# 8266_DIYIOT_Board_B_DS_V_G.net
KiCad netlist of a schematic drawn in EAGLE
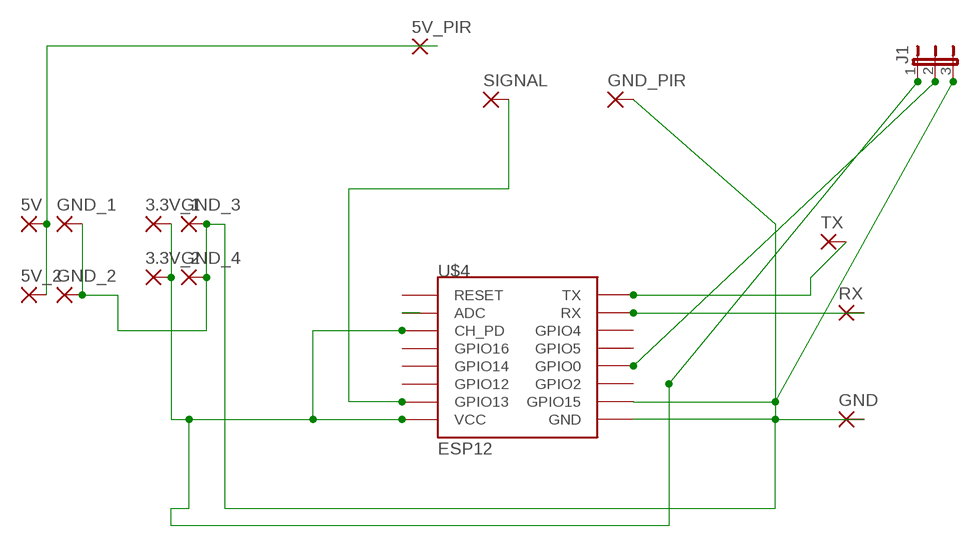
[diagram p0: schematic, sheet 1]

(export (version "E")
  (design (tool "Eeschema 10.0.6"))
  (components
    (comp (ref "3.3V_1")
      (value "2,15/1,0")
      (footprint "eagle-import:2,15_1,0")
      (libsource (lib "eagle-import") (part "2,15/1,0"))
    )
    (comp (ref "3.3V_2")
      (value "2,15/1,0")
      (footprint "eagle-import:2,15_1,0")
      (libsource (lib "eagle-import") (part "2,15/1,0"))
    )
    (comp (ref "5V")
      (value "2,15/1,0")
      (footprint "eagle-import:2,15_1,0")
      (libsource (lib "eagle-import") (part "2,15/1,0"))
    )
    (comp (ref "5V_2")
      (value "2,15/1,0")
      (footprint "eagle-import:2,15_1,0")
      (libsource (lib "eagle-import") (part "2,15/1,0"))
    )
    (comp (ref "5V_PIR")
      (value "2,15/1,0")
      (footprint "eagle-import:2,15_1,0")
      (libsource (lib "eagle-import") (part "2,15/1,0"))
    )
    (comp (ref "GND")
      (value "2,15/1,0")
      (footprint "eagle-import:2,15_1,0")
      (libsource (lib "eagle-import") (part "2,15/1,0"))
    )
    (comp (ref "GND_1")
      (value "2,15/1,0")
      (footprint "eagle-import:2,15_1,0")
      (libsource (lib "eagle-import") (part "2,15/1,0"))
    )
    (comp (ref "GND_2")
      (value "2,15/1,0")
      (footprint "eagle-import:2,15_1,0")
      (libsource (lib "eagle-import") (part "2,15/1,0"))
    )
    (comp (ref "GND_3")
      (value "2,15/1,0")
      (footprint "eagle-import:2,15_1,0")
      (libsource (lib "eagle-import") (part "2,15/1,0"))
    )
    (comp (ref "GND_4")
      (value "2,15/1,0")
      (footprint "eagle-import:2,15_1,0")
      (libsource (lib "eagle-import") (part "2,15/1,0"))
    )
    (comp (ref "GND_PIR")
      (value "2,15/1,0")
      (footprint "eagle-import:2,15_1,0")
      (libsource (lib "eagle-import") (part "2,15/1,0"))
    )
    (comp (ref "J1")
      (value "JP2E")
      (footprint "eagle-import:JP2")
      (libsource (lib "eagle-import") (part "JP2E"))
    )
    (comp (ref "RX")
      (value "2,15/1,0")
      (footprint "eagle-import:2,15_1,0")
      (libsource (lib "eagle-import") (part "2,15/1,0"))
    )
    (comp (ref "SIGNAL")
      (value "2,15/1,0")
      (footprint "eagle-import:2,15_1,0")
      (libsource (lib "eagle-import") (part "2,15/1,0"))
    )
    (comp (ref "TX")
      (value "2,15/1,0")
      (footprint "eagle-import:2,15_1,0")
      (libsource (lib "eagle-import") (part "2,15/1,0"))
    )
    (comp (ref "U$4")
      (value "ESP12")
      (footprint "eagle-import:ESP12")
      (libsource (lib "eagle-import") (part "ESP12"))
    )
  )
  (nets
    (net (code "1") (name "/5V") (class "Default")
      (node (ref "5V") (pin "1") (pinfunction "P_1") (pintype "passive"))
      (node (ref "5V_2") (pin "1") (pinfunction "P_1") (pintype "passive"))
      (node (ref "5V_PIR") (pin "1") (pinfunction "P_1") (pintype "passive"))
      (node (ref "GND") (pin "1") (pinfunction "P_1") (pintype "passive"))
      (node (ref "GND_1") (pin "1") (pinfunction "P_1") (pintype "passive"))
      (node (ref "GND_2") (pin "1") (pinfunction "P_1") (pintype "passive"))
      (node (ref "GND_3") (pin "1") (pinfunction "P_1") (pintype "passive"))
      (node (ref "GND_4") (pin "1") (pinfunction "P_1") (pintype "passive"))
      (node (ref "GND_PIR") (pin "1") (pinfunction "P_1") (pintype "passive"))
      (node (ref "J1") (pin "3") (pinfunction "3_3") (pintype "passive"))
      (node (ref "U$4") (pin "GND") (pinfunction "GND_GND") (pintype "bidirectional"))
      (node (ref "U$4") (pin "GPIO15") (pinfunction "GPIO15_GPIO15") (pintype "bidirectional"))
    )
    (net (code "2") (name "Net-(3.3V_1-P)") (class "Default")
      (node (ref "3.3V_1") (pin "1") (pinfunction "P_1") (pintype "passive"))
      (node (ref "3.3V_2") (pin "1") (pinfunction "P_1") (pintype "passive"))
      (node (ref "J1") (pin "1") (pinfunction "1_1") (pintype "passive"))
      (node (ref "U$4") (pin "CH_PD") (pinfunction "CH_PD_CH_PD") (pintype "bidirectional"))
      (node (ref "U$4") (pin "VCC") (pinfunction "VCC_VCC") (pintype "bidirectional"))
    )
    (net (code "3") (name "Net-(J1-Pad2)") (class "Default")
      (node (ref "J1") (pin "2") (pinfunction "2_2") (pintype "passive"))
      (node (ref "U$4") (pin "GPIO0") (pinfunction "GPIO0_GPIO0") (pintype "bidirectional"))
    )
    (net (code "4") (name "Net-(RX-P)") (class "Default")
      (node (ref "RX") (pin "1") (pinfunction "P_1") (pintype "passive"))
      (node (ref "U$4") (pin "RX") (pinfunction "RX_RX") (pintype "bidirectional"))
    )
    (net (code "5") (name "Net-(SIGNAL-P)") (class "Default")
      (node (ref "SIGNAL") (pin "1") (pinfunction "P_1") (pintype "passive"))
      (node (ref "U$4") (pin "GPIO13") (pinfunction "GPIO13_GPIO13") (pintype "bidirectional"))
    )
    (net (code "6") (name "Net-(TX-P)") (class "Default")
      (node (ref "TX") (pin "1") (pinfunction "P_1") (pintype "passive"))
      (node (ref "U$4") (pin "TX") (pinfunction "TX_TX") (pintype "bidirectional"))
    )
    (net (code "7") (name "unconnected-(U$4-PadADC)") (class "Default")
      (node (ref "U$4") (pin "ADC") (pinfunction "ADC_ADC") (pintype "bidirectional"))
    )
    (net (code "8") (name "unconnected-(U$4-PadGPIO2)") (class "Default")
      (node (ref "U$4") (pin "GPIO2") (pinfunction "GPIO2_GPIO2") (pintype "bidirectional"))
    )
    (net (code "9") (name "unconnected-(U$4-PadGPIO4)") (class "Default")
      (node (ref "U$4") (pin "GPIO4") (pinfunction "GPIO4_GPIO4") (pintype "bidirectional"))
    )
    (net (code "10") (name "unconnected-(U$4-PadGPIO5)") (class "Default")
      (node (ref "U$4") (pin "GPIO5") (pinfunction "GPIO5_GPIO5") (pintype "bidirectional"))
    )
    (net (code "11") (name "unconnected-(U$4-PadGPIO12)") (class "Default")
      (node (ref "U$4") (pin "GPIO12") (pinfunction "GPIO12_GPIO12") (pintype "bidirectional"))
    )
    (net (code "12") (name "unconnected-(U$4-PadGPIO14)") (class "Default")
      (node (ref "U$4") (pin "GPIO14") (pinfunction "GPIO14_GPIO14") (pintype "bidirectional"))
    )
    (net (code "13") (name "unconnected-(U$4-PadGPIO16)") (class "Default")
      (node (ref "U$4") (pin "GPIO16") (pinfunction "GPIO16_GPIO16") (pintype "bidirectional"))
    )
    (net (code "14") (name "unconnected-(U$4-PadRESET)") (class "Default")
      (node (ref "U$4") (pin "RESET") (pinfunction "RESET_RESET") (pintype "bidirectional"))
    )
  )
)
